# ADC1.net
KiCad netlist of a schematic drawn in Altium Designer
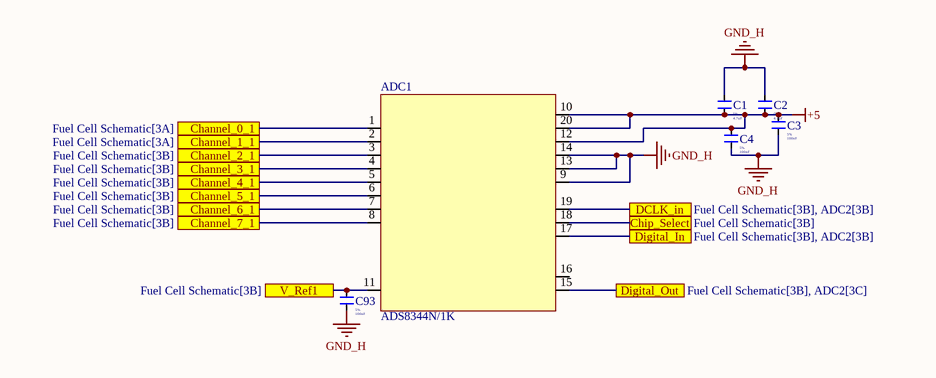
[diagram p0: ADC1.SchDoc]

(export (version "E")
  (design (tool "Eeschema 10.0.6"))
  (components
    (comp (ref "ADC1")
      (value "ADS8344N/1K")
      (footprint "ADS8344")
      (description "IC ADC 16BIT SAR 20SSOP")
      (fields (field (name "MANUFACTURER") "Texas Instruments"))
      (libsource (lib "Schlib1") (part "ADS8344N/1K"))
    )
    (comp (ref "C1")
      (value "~")
      (footprint "Capacitor_Kemet_0805")
      (description "CAP CER 4.7UF 16V X7R 0805")
      (fields
        (field (name "MANUFACTURER") "KEMET")
        (field (name "MANUFACTURER PART NUMBER") "C0805C475J4RACAUTO")
        (field (name "TOLERANCE") "5%")
        (field (name "CAPACITANCE") "4.7uF")
      )
      (libsource (lib "Schlib1") (part "C0805C475J4RACAUTO"))
    )
    (comp (ref "C2")
      (value "~")
      (footprint "Capacitor_Kemet_0805")
      (description "CAP CER 4.7UF 16V X7R 0805")
      (fields
        (field (name "MANUFACTURER") "KEMET")
        (field (name "MANUFACTURER PART NUMBER") "C0805C475J4RACAUTO")
        (field (name "TOLERANCE") "5%")
        (field (name "CAPACITANCE") "4.7uF")
      )
      (libsource (lib "Schlib1") (part "C0805C475J4RACAUTO"))
    )
    (comp (ref "C3")
      (value "~")
      (footprint "Capacitor_Kemet_0805")
      (description "Cap Ceramic 0.1uF 16V X7R 5% SMD 0805 125°C Plastic T/R")
      (fields
        (field (name "MANUFACTURER") "KEMET")
        (field (name "MANUFACTURER PART NUMBER") "C0805C104J4RACTU")
        (field (name "DISSIPATION FACTOR") "5%")
        (field (name "CAPACITANCE") "100nF")
      )
      (libsource (lib "Schlib1") (part "C0805C104J4RACTU"))
    )
    (comp (ref "C4")
      (value "~")
      (footprint "Capacitor_Kemet_0805")
      (description "Cap Ceramic 0.1uF 16V X7R 5% SMD 0805 125°C Plastic T/R")
      (fields
        (field (name "MANUFACTURER") "KEMET")
        (field (name "MANUFACTURER PART NUMBER") "C0805C104J4RACTU")
        (field (name "DISSIPATION FACTOR") "5%")
        (field (name "CAPACITANCE") "100nF")
      )
      (libsource (lib "Schlib1") (part "C0805C104J4RACTU"))
    )
    (comp (ref "C93")
      (value "~")
      (footprint "Capacitor_Kemet_0805")
      (description "Cap Ceramic 0.1uF 16V X7R 5% SMD 0805 125°C Plastic T/R")
      (fields
        (field (name "MANUFACTURER") "KEMET")
        (field (name "MANUFACTURER PART NUMBER") "C0805C104J4RACTU")
        (field (name "DISSIPATION FACTOR") "5%")
        (field (name "CAPACITANCE") "100nF")
      )
      (libsource (lib "Schlib1") (part "C0805C104J4RACTU"))
    )
  )
  (nets
    (net (code "1") (name "+5") (class "Default")
      (node (ref "ADC1") (pin "10") (pinfunction "Shutdown_10") (pintype "passive"))
      (node (ref "ADC1") (pin "12") (pinfunction "+VCC_12") (pintype "passive"))
      (node (ref "ADC1") (pin "20") (pinfunction "+VCC_20") (pintype "passive"))
      (node (ref "C1") (pin "1") (pinfunction "1_1") (pintype "passive"))
      (node (ref "C2") (pin "1") (pinfunction "1_1") (pintype "passive"))
      (node (ref "C3") (pin "2") (pinfunction "2_2") (pintype "passive"))
      (node (ref "C4") (pin "2") (pinfunction "2_2") (pintype "passive"))
    )
    (net (code "2") (name "/Channel_0_1") (class "Default")
      (node (ref "ADC1") (pin "1") (pinfunction "Channel_0_1") (pintype "passive"))
    )
    (net (code "3") (name "/Channel_1_1") (class "Default")
      (node (ref "ADC1") (pin "2") (pinfunction "Channel_1_2") (pintype "passive"))
    )
    (net (code "4") (name "/Channel_2_1") (class "Default")
      (node (ref "ADC1") (pin "3") (pinfunction "Channel_2_3") (pintype "passive"))
    )
    (net (code "5") (name "/Channel_3_1") (class "Default")
      (node (ref "ADC1") (pin "4") (pinfunction "Channel_3_4") (pintype "passive"))
    )
    (net (code "6") (name "/Channel_4_1") (class "Default")
      (node (ref "ADC1") (pin "5") (pinfunction "Channel_4_5") (pintype "passive"))
    )
    (net (code "7") (name "/Channel_5_1") (class "Default")
      (node (ref "ADC1") (pin "6") (pinfunction "Channel_5_6") (pintype "passive"))
    )
    (net (code "8") (name "/Channel_6_1") (class "Default")
      (node (ref "ADC1") (pin "7") (pinfunction "Channel_6_7") (pintype "passive"))
    )
    (net (code "9") (name "/Channel_7_1") (class "Default")
      (node (ref "ADC1") (pin "8") (pinfunction "Channel_7_8") (pintype "passive"))
    )
    (net (code "10") (name "/Chip_Select") (class "Default")
      (node (ref "ADC1") (pin "18") (pinfunction "Chip_Select_18") (pintype "passive"))
    )
    (net (code "11") (name "/DCLK_in") (class "Default")
      (node (ref "ADC1") (pin "19") (pinfunction "Digital_Clock_19") (pintype "passive"))
    )
    (net (code "12") (name "/Digital_In") (class "Default")
      (node (ref "ADC1") (pin "17") (pinfunction "Digital_In_17") (pintype "passive"))
    )
    (net (code "13") (name "/Digital_Out") (class "Default")
      (node (ref "ADC1") (pin "15") (pinfunction "Digital_Out_15") (pintype "passive"))
    )
    (net (code "14") (name "/V_Ref1") (class "Default")
      (node (ref "ADC1") (pin "11") (pinfunction "V_Reference_11") (pintype "passive"))
      (node (ref "C93") (pin "2") (pinfunction "2_2") (pintype "passive"))
    )
    (net (code "15") (name "GND_H") (class "Default")
      (node (ref "ADC1") (pin "13") (pinfunction "Ground_13") (pintype "passive"))
      (node (ref "ADC1") (pin "14") (pinfunction "Ground_14") (pintype "passive"))
      (node (ref "ADC1") (pin "9") (pinfunction "Common_Reference_9") (pintype "passive"))
      (node (ref "C1") (pin "2") (pinfunction "2_2") (pintype "passive"))
      (node (ref "C2") (pin "2") (pinfunction "2_2") (pintype "passive"))
      (node (ref "C3") (pin "1") (pinfunction "1_1") (pintype "passive"))
      (node (ref "C4") (pin "1") (pinfunction "1_1") (pintype "passive"))
      (node (ref "C93") (pin "1") (pinfunction "1_1") (pintype "passive"))
    )
    (net (code "16") (name "unconnected-(ADC1-Busy-Pad16)") (class "Default")
      (node (ref "ADC1") (pin "16") (pinfunction "Busy_16") (pintype "passive"))
    )
  )
)
